# 4channelpot.net
KiCad netlist of a schematic drawn in EAGLE
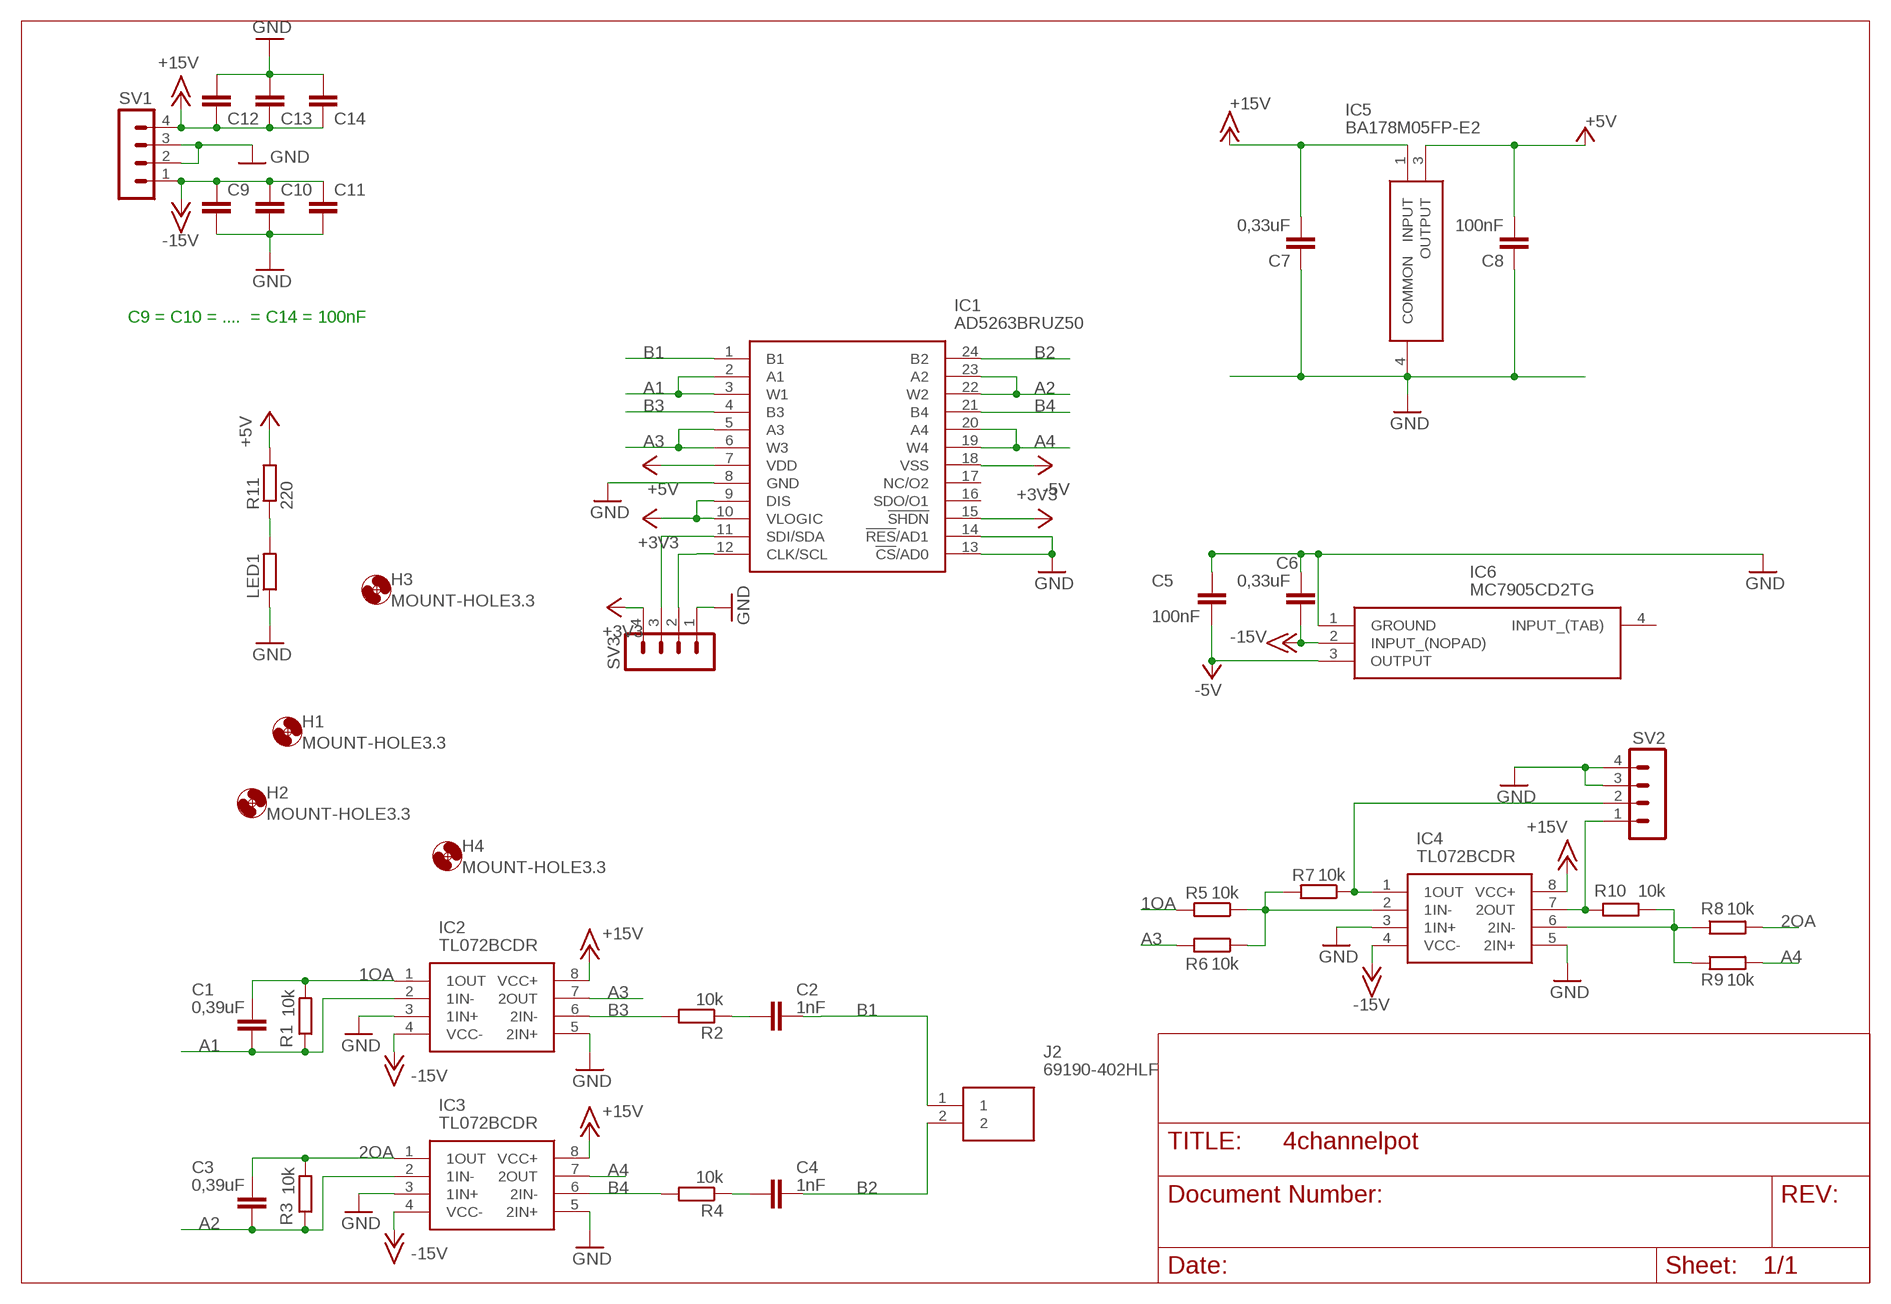
[diagram p0: schematic, sheet 1]

(export (version "E")
  (design (tool "Eeschema 10.0.6"))
  (components
    (comp (ref "C1")
      (value "0,39uF")
      (footprint "eagle-import:C0805")
      (libsource (lib "eagle-import") (part "C-EUC0805"))
    )
    (comp (ref "C2")
      (value "1nF")
      (footprint "eagle-import:C0805")
      (libsource (lib "eagle-import") (part "C-EUC0805"))
    )
    (comp (ref "C3")
      (value "0,39uF")
      (footprint "eagle-import:C0805")
      (libsource (lib "eagle-import") (part "C-EUC0805"))
    )
    (comp (ref "C4")
      (value "1nF")
      (footprint "eagle-import:C0805")
      (libsource (lib "eagle-import") (part "C-EUC0805"))
    )
    (comp (ref "C5")
      (value "100nF")
      (footprint "eagle-import:C0805")
      (libsource (lib "eagle-import") (part "C-EUC0805"))
    )
    (comp (ref "C6")
      (value "0,33uF")
      (footprint "eagle-import:C0805")
      (libsource (lib "eagle-import") (part "C-EUC0805"))
    )
    (comp (ref "C7")
      (value "0,33uF")
      (footprint "eagle-import:C0805")
      (libsource (lib "eagle-import") (part "C-EUC0805"))
    )
    (comp (ref "C8")
      (value "100nF")
      (footprint "eagle-import:C0805")
      (libsource (lib "eagle-import") (part "C-EUC0805"))
    )
    (comp (ref "C9")
      (value "C-EUC0805")
      (footprint "eagle-import:C0805")
      (libsource (lib "eagle-import") (part "C-EUC0805"))
    )
    (comp (ref "C10")
      (value "C-EUC0805")
      (footprint "eagle-import:C0805")
      (libsource (lib "eagle-import") (part "C-EUC0805"))
    )
    (comp (ref "C11")
      (value "C-EUC0805")
      (footprint "eagle-import:C0805")
      (libsource (lib "eagle-import") (part "C-EUC0805"))
    )
    (comp (ref "C12")
      (value "C-EUC0805")
      (footprint "eagle-import:C0805")
      (libsource (lib "eagle-import") (part "C-EUC0805"))
    )
    (comp (ref "C13")
      (value "C-EUC0805")
      (footprint "eagle-import:C0805")
      (libsource (lib "eagle-import") (part "C-EUC0805"))
    )
    (comp (ref "C14")
      (value "C-EUC0805")
      (footprint "eagle-import:C0805")
      (libsource (lib "eagle-import") (part "C-EUC0805"))
    )
    (comp (ref "H1")
      (value "MOUNT-HOLE3.3")
      (footprint "eagle-import:3,3")
      (libsource (lib "eagle-import") (part "MOUNT-HOLE3.3"))
    )
    (comp (ref "H2")
      (value "MOUNT-HOLE3.3")
      (footprint "eagle-import:3,3")
      (libsource (lib "eagle-import") (part "MOUNT-HOLE3.3"))
    )
    (comp (ref "H3")
      (value "MOUNT-HOLE3.3")
      (footprint "eagle-import:3,3")
      (libsource (lib "eagle-import") (part "MOUNT-HOLE3.3"))
    )
    (comp (ref "H4")
      (value "MOUNT-HOLE3.3")
      (footprint "eagle-import:3,3")
      (libsource (lib "eagle-import") (part "MOUNT-HOLE3.3"))
    )
    (comp (ref "IC1")
      (value "AD5263BRUZ50")
      (footprint "eagle-import:SOP65P640X120-24N")
      (fields (field (name "MOUSER_PART_NUMBER") "584-AD5263BRUZ50"))
      (libsource (lib "eagle-import") (part "AD5263BRUZ50"))
    )
    (comp (ref "IC2")
      (value "TL072BCDR")
      (footprint "eagle-import:SOIC127P600X175-8N")
      (fields (field (name "MOUSER_PART_NUMBER") "595-TL072BCDR"))
      (libsource (lib "eagle-import") (part "TL072BCDR"))
    )
    (comp (ref "IC3")
      (value "TL072BCDR")
      (footprint "eagle-import:SOIC127P600X175-8N")
      (fields (field (name "MOUSER_PART_NUMBER") "595-TL072BCDR"))
      (libsource (lib "eagle-import") (part "TL072BCDR"))
    )
    (comp (ref "IC4")
      (value "TL072BCDR")
      (footprint "eagle-import:SOIC127P600X175-8N")
      (fields (field (name "MOUSER_PART_NUMBER") "595-TL072BCDR"))
      (libsource (lib "eagle-import") (part "TL072BCDR"))
    )
    (comp (ref "IC5")
      (value "BA178M05FP-E2")
      (footprint "eagle-import:BD750L5FPCE2")
      (fields (field (name "MOUSER_PART_NUMBER") "755-BA178M05FP-E2"))
      (libsource (lib "eagle-import") (part "BA178M05FP-E2"))
    )
    (comp (ref "IC6")
      (value "MC7905CD2TG")
      (footprint "eagle-import:TO254P1420X457-4N")
      (fields (field (name "MOUSER_PART_NUMBER") "863-MC7905CD2TG"))
      (libsource (lib "eagle-import") (part "MC7905CD2TG"))
    )
    (comp (ref "J2")
      (value "69190-402HLF")
      (footprint "eagle-import:HDRV2W90P0X254_1X2_508X241X858")
      (fields (field (name "RS_PART_NUMBER") "8632731"))
      (libsource (lib "eagle-import") (part "69190-402HLF"))
    )
    (comp (ref "LED1")
      (value "R-EU_R0805")
      (footprint "eagle-import:R0805")
      (libsource (lib "eagle-import") (part "R-EU_R0805"))
    )
    (comp (ref "R1")
      (value "10k")
      (footprint "eagle-import:R0805")
      (libsource (lib "eagle-import") (part "R-EU_R0805"))
    )
    (comp (ref "R2")
      (value "10k")
      (footprint "eagle-import:R0805")
      (libsource (lib "eagle-import") (part "R-EU_R0805"))
    )
    (comp (ref "R3")
      (value "10k")
      (footprint "eagle-import:R0805")
      (libsource (lib "eagle-import") (part "R-EU_R0805"))
    )
    (comp (ref "R4")
      (value "10k")
      (footprint "eagle-import:R0805")
      (libsource (lib "eagle-import") (part "R-EU_R0805"))
    )
    (comp (ref "R5")
      (value "10k")
      (footprint "eagle-import:R0805")
      (libsource (lib "eagle-import") (part "R-EU_R0805"))
    )
    (comp (ref "R6")
      (value "10k")
      (footprint "eagle-import:R0805")
      (libsource (lib "eagle-import") (part "R-EU_R0805"))
    )
    (comp (ref "R7")
      (value "10k")
      (footprint "eagle-import:R0805")
      (libsource (lib "eagle-import") (part "R-EU_R0805"))
    )
    (comp (ref "R8")
      (value "10k")
      (footprint "eagle-import:R0805")
      (libsource (lib "eagle-import") (part "R-EU_R0805"))
    )
    (comp (ref "R9")
      (value "10k")
      (footprint "eagle-import:R0805")
      (libsource (lib "eagle-import") (part "R-EU_R0805"))
    )
    (comp (ref "R10")
      (value "10k")
      (footprint "eagle-import:R0805")
      (libsource (lib "eagle-import") (part "R-EU_R0805"))
    )
    (comp (ref "R11")
      (value "220")
      (footprint "eagle-import:R0805")
      (libsource (lib "eagle-import") (part "R-EU_R0805"))
    )
    (comp (ref "SV1")
      (value "MA04-1")
      (footprint "eagle-import:MA04-1")
      (libsource (lib "eagle-import") (part "MA04-1"))
    )
    (comp (ref "SV2")
      (value "MA04-1")
      (footprint "eagle-import:MA04-1")
      (libsource (lib "eagle-import") (part "MA04-1"))
    )
    (comp (ref "SV3")
      (value "MA04-1")
      (footprint "eagle-import:MA04-1")
      (libsource (lib "eagle-import") (part "MA04-1"))
    )
  )
  (nets
    (net (code "1") (name "+3V3") (class "Default")
      (node (ref "IC1") (pin "10") (pinfunction "VLOGIC_10") (pintype "bidirectional"))
      (node (ref "IC1") (pin "15") (pinfunction "~{SHDN}_15") (pintype "bidirectional"))
      (node (ref "IC1") (pin "9") (pinfunction "DIS_9") (pintype "bidirectional"))
      (node (ref "SV3") (pin "4") (pinfunction "4_4") (pintype "passive"))
    )
    (net (code "2") (name "+5V") (class "Default")
      (node (ref "C8") (pin "2") (pinfunction "2_2") (pintype "passive"))
      (node (ref "IC1") (pin "7") (pinfunction "VDD_7") (pintype "bidirectional"))
      (node (ref "IC5") (pin "3") (pinfunction "OUTPUT_3") (pintype "bidirectional"))
      (node (ref "R11") (pin "2") (pinfunction "2_2") (pintype "passive"))
    )
    (net (code "3") (name "+15V") (class "Default")
      (node (ref "C12") (pin "1") (pinfunction "1_1") (pintype "passive"))
      (node (ref "C13") (pin "1") (pinfunction "1_1") (pintype "passive"))
      (node (ref "C14") (pin "1") (pinfunction "1_1") (pintype "passive"))
      (node (ref "C7") (pin "2") (pinfunction "2_2") (pintype "passive"))
      (node (ref "IC2") (pin "8") (pinfunction "VCC+_8") (pintype "bidirectional"))
      (node (ref "IC3") (pin "8") (pinfunction "VCC+_8") (pintype "bidirectional"))
      (node (ref "IC4") (pin "8") (pinfunction "VCC+_8") (pintype "bidirectional"))
      (node (ref "IC5") (pin "1") (pinfunction "INPUT_1") (pintype "bidirectional"))
      (node (ref "SV1") (pin "4") (pinfunction "4_4") (pintype "passive"))
    )
    (net (code "4") (name "-5V") (class "Default")
      (node (ref "C5") (pin "2") (pinfunction "2_2") (pintype "passive"))
      (node (ref "IC1") (pin "18") (pinfunction "VSS_18") (pintype "bidirectional"))
      (node (ref "IC6") (pin "3") (pinfunction "OUTPUT_3") (pintype "output"))
    )
    (net (code "5") (name "-15V") (class "Default")
      (node (ref "C10") (pin "1") (pinfunction "1_1") (pintype "passive"))
      (node (ref "C11") (pin "1") (pinfunction "1_1") (pintype "passive"))
      (node (ref "C6") (pin "2") (pinfunction "2_2") (pintype "passive"))
      (node (ref "C9") (pin "1") (pinfunction "1_1") (pintype "passive"))
      (node (ref "IC2") (pin "4") (pinfunction "VCC-_4") (pintype "bidirectional"))
      (node (ref "IC3") (pin "4") (pinfunction "VCC-_4") (pintype "bidirectional"))
      (node (ref "IC4") (pin "4") (pinfunction "VCC-_4") (pintype "bidirectional"))
      (node (ref "IC6") (pin "2") (pinfunction "INPUT_(NOPAD)_2") (pintype "input"))
      (node (ref "SV1") (pin "1") (pinfunction "1_1") (pintype "passive"))
    )
    (net (code "6") (name "/1OA") (class "Default")
      (node (ref "C1") (pin "1") (pinfunction "1_1") (pintype "passive"))
      (node (ref "IC2") (pin "1") (pinfunction "1OUT_1") (pintype "bidirectional"))
      (node (ref "R1") (pin "2") (pinfunction "2_2") (pintype "passive"))
      (node (ref "R5") (pin "2") (pinfunction "2_2") (pintype "passive"))
    )
    (net (code "7") (name "/2OA") (class "Default")
      (node (ref "C3") (pin "1") (pinfunction "1_1") (pintype "passive"))
      (node (ref "IC3") (pin "1") (pinfunction "1OUT_1") (pintype "bidirectional"))
      (node (ref "R3") (pin "2") (pinfunction "2_2") (pintype "passive"))
      (node (ref "R8") (pin "2") (pinfunction "2_2") (pintype "passive"))
    )
    (net (code "8") (name "/A1") (class "Default")
      (node (ref "C1") (pin "2") (pinfunction "2_2") (pintype "passive"))
      (node (ref "IC1") (pin "2") (pinfunction "A1_2") (pintype "bidirectional"))
      (node (ref "IC1") (pin "3") (pinfunction "W1_3") (pintype "bidirectional"))
      (node (ref "IC2") (pin "2") (pinfunction "1IN-_2") (pintype "bidirectional"))
      (node (ref "R1") (pin "1") (pinfunction "1_1") (pintype "passive"))
    )
    (net (code "9") (name "/A2") (class "Default")
      (node (ref "C3") (pin "2") (pinfunction "2_2") (pintype "passive"))
      (node (ref "IC1") (pin "22") (pinfunction "W2_22") (pintype "bidirectional"))
      (node (ref "IC1") (pin "23") (pinfunction "A2_23") (pintype "bidirectional"))
      (node (ref "IC3") (pin "2") (pinfunction "1IN-_2") (pintype "bidirectional"))
      (node (ref "R3") (pin "1") (pinfunction "1_1") (pintype "passive"))
    )
    (net (code "10") (name "/A3") (class "Default")
      (node (ref "IC1") (pin "5") (pinfunction "A3_5") (pintype "bidirectional"))
      (node (ref "IC1") (pin "6") (pinfunction "W3_6") (pintype "bidirectional"))
      (node (ref "IC2") (pin "7") (pinfunction "2OUT_7") (pintype "bidirectional"))
      (node (ref "R6") (pin "2") (pinfunction "2_2") (pintype "passive"))
    )
    (net (code "11") (name "/A4") (class "Default")
      (node (ref "IC1") (pin "19") (pinfunction "W4_19") (pintype "bidirectional"))
      (node (ref "IC1") (pin "20") (pinfunction "A4_20") (pintype "bidirectional"))
      (node (ref "IC3") (pin "7") (pinfunction "2OUT_7") (pintype "bidirectional"))
      (node (ref "R9") (pin "2") (pinfunction "2_2") (pintype "passive"))
    )
    (net (code "12") (name "/B1") (class "Default")
      (node (ref "C2") (pin "1") (pinfunction "1_1") (pintype "passive"))
      (node (ref "IC1") (pin "1") (pinfunction "B1_1") (pintype "bidirectional"))
      (node (ref "J2") (pin "1") (pinfunction "1_1") (pintype "bidirectional"))
    )
    (net (code "13") (name "/B2") (class "Default")
      (node (ref "C4") (pin "1") (pinfunction "1_1") (pintype "passive"))
      (node (ref "IC1") (pin "24") (pinfunction "B2_24") (pintype "bidirectional"))
      (node (ref "J2") (pin "2") (pinfunction "2_2") (pintype "bidirectional"))
    )
    (net (code "14") (name "/B3") (class "Default")
      (node (ref "IC1") (pin "4") (pinfunction "B3_4") (pintype "bidirectional"))
      (node (ref "IC2") (pin "6") (pinfunction "2IN-_6") (pintype "bidirectional"))
      (node (ref "R2") (pin "2") (pinfunction "2_2") (pintype "passive"))
    )
    (net (code "15") (name "/B4") (class "Default")
      (node (ref "IC1") (pin "21") (pinfunction "B4_21") (pintype "bidirectional"))
      (node (ref "IC3") (pin "6") (pinfunction "2IN-_6") (pintype "bidirectional"))
      (node (ref "R4") (pin "2") (pinfunction "2_2") (pintype "passive"))
    )
    (net (code "16") (name "GND") (class "Default")
      (node (ref "C10") (pin "2") (pinfunction "2_2") (pintype "passive"))
      (node (ref "C11") (pin "2") (pinfunction "2_2") (pintype "passive"))
      (node (ref "C12") (pin "2") (pinfunction "2_2") (pintype "passive"))
      (node (ref "C13") (pin "2") (pinfunction "2_2") (pintype "passive"))
      (node (ref "C14") (pin "2") (pinfunction "2_2") (pintype "passive"))
      (node (ref "C5") (pin "1") (pinfunction "1_1") (pintype "passive"))
      (node (ref "C6") (pin "1") (pinfunction "1_1") (pintype "passive"))
      (node (ref "C7") (pin "1") (pinfunction "1_1") (pintype "passive"))
      (node (ref "C8") (pin "1") (pinfunction "1_1") (pintype "passive"))
      (node (ref "C9") (pin "2") (pinfunction "2_2") (pintype "passive"))
      (node (ref "IC1") (pin "13") (pinfunction "~{CS}/AD0_13") (pintype "bidirectional"))
      (node (ref "IC1") (pin "14") (pinfunction "~{RES}/AD1_14") (pintype "bidirectional"))
      (node (ref "IC1") (pin "8") (pinfunction "GND_8") (pintype "bidirectional"))
      (node (ref "IC2") (pin "3") (pinfunction "1IN+_3") (pintype "bidirectional"))
      (node (ref "IC2") (pin "5") (pinfunction "2IN+_5") (pintype "bidirectional"))
      (node (ref "IC3") (pin "3") (pinfunction "1IN+_3") (pintype "bidirectional"))
      (node (ref "IC3") (pin "5") (pinfunction "2IN+_5") (pintype "bidirectional"))
      (node (ref "IC4") (pin "3") (pinfunction "1IN+_3") (pintype "bidirectional"))
      (node (ref "IC4") (pin "5") (pinfunction "2IN+_5") (pintype "bidirectional"))
      (node (ref "IC5") (pin "4") (pinfunction "COMMON_4") (pintype "bidirectional"))
      (node (ref "IC6") (pin "1") (pinfunction "GROUND_1") (pintype "bidirectional"))
      (node (ref "LED1") (pin "1") (pinfunction "1_1") (pintype "passive"))
      (node (ref "SV1") (pin "2") (pinfunction "2_2") (pintype "passive"))
      (node (ref "SV1") (pin "3") (pinfunction "3_3") (pintype "passive"))
      (node (ref "SV2") (pin "3") (pinfunction "3_3") (pintype "passive"))
      (node (ref "SV2") (pin "4") (pinfunction "4_4") (pintype "passive"))
      (node (ref "SV3") (pin "1") (pinfunction "1_1") (pintype "passive"))
    )
    (net (code "17") (name "Net-(C2-Pad2)") (class "Default")
      (node (ref "C2") (pin "2") (pinfunction "2_2") (pintype "passive"))
      (node (ref "R2") (pin "1") (pinfunction "1_1") (pintype "passive"))
    )
    (net (code "18") (name "Net-(C4-Pad2)") (class "Default")
      (node (ref "C4") (pin "2") (pinfunction "2_2") (pintype "passive"))
      (node (ref "R4") (pin "1") (pinfunction "1_1") (pintype "passive"))
    )
    (net (code "19") (name "Net-(IC1-CLK{slash}SCL)") (class "Default")
      (node (ref "IC1") (pin "12") (pinfunction "CLK/SCL_12") (pintype "bidirectional"))
      (node (ref "SV3") (pin "2") (pinfunction "2_2") (pintype "passive"))
    )
    (net (code "20") (name "Net-(IC1-SDI{slash}SDA)") (class "Default")
      (node (ref "IC1") (pin "11") (pinfunction "SDI/SDA_11") (pintype "bidirectional"))
      (node (ref "SV3") (pin "3") (pinfunction "3_3") (pintype "passive"))
    )
    (net (code "21") (name "Net-(IC4-1IN-)") (class "Default")
      (node (ref "IC4") (pin "2") (pinfunction "1IN-_2") (pintype "bidirectional"))
      (node (ref "R5") (pin "1") (pinfunction "1_1") (pintype "passive"))
      (node (ref "R6") (pin "1") (pinfunction "1_1") (pintype "passive"))
      (node (ref "R7") (pin "2") (pinfunction "2_2") (pintype "passive"))
    )
    (net (code "22") (name "Net-(IC4-1OUT)") (class "Default")
      (node (ref "IC4") (pin "1") (pinfunction "1OUT_1") (pintype "bidirectional"))
      (node (ref "R7") (pin "1") (pinfunction "1_1") (pintype "passive"))
      (node (ref "SV2") (pin "2") (pinfunction "2_2") (pintype "passive"))
    )
    (net (code "23") (name "Net-(IC4-2IN-)") (class "Default")
      (node (ref "IC4") (pin "6") (pinfunction "2IN-_6") (pintype "bidirectional"))
      (node (ref "R10") (pin "2") (pinfunction "2_2") (pintype "passive"))
      (node (ref "R8") (pin "1") (pinfunction "1_1") (pintype "passive"))
      (node (ref "R9") (pin "1") (pinfunction "1_1") (pintype "passive"))
    )
    (net (code "24") (name "Net-(IC4-2OUT)") (class "Default")
      (node (ref "IC4") (pin "7") (pinfunction "2OUT_7") (pintype "bidirectional"))
      (node (ref "R10") (pin "1") (pinfunction "1_1") (pintype "passive"))
      (node (ref "SV2") (pin "1") (pinfunction "1_1") (pintype "passive"))
    )
    (net (code "25") (name "Net-(LED1-Pad2)") (class "Default")
      (node (ref "LED1") (pin "2") (pinfunction "2_2") (pintype "passive"))
      (node (ref "R11") (pin "1") (pinfunction "1_1") (pintype "passive"))
    )
    (net (code "26") (name "unconnected-(IC1-NC{slash}O2-Pad17)") (class "Default")
      (node (ref "IC1") (pin "17") (pinfunction "NC/O2_17") (pintype "bidirectional"))
    )
    (net (code "27") (name "unconnected-(IC1-SDO{slash}O1-Pad16)") (class "Default")
      (node (ref "IC1") (pin "16") (pinfunction "SDO/O1_16") (pintype "bidirectional"))
    )
    (net (code "28") (name "unconnected-(IC6-INPUT_(TAB)-Pad4)") (class "Default")
      (node (ref "IC6") (pin "4") (pinfunction "INPUT_(TAB)_4") (pintype "input"))
    )
  )
)
